# 05-Power-V5P0.net
KiCad netlist of a schematic drawn in Altium Designer
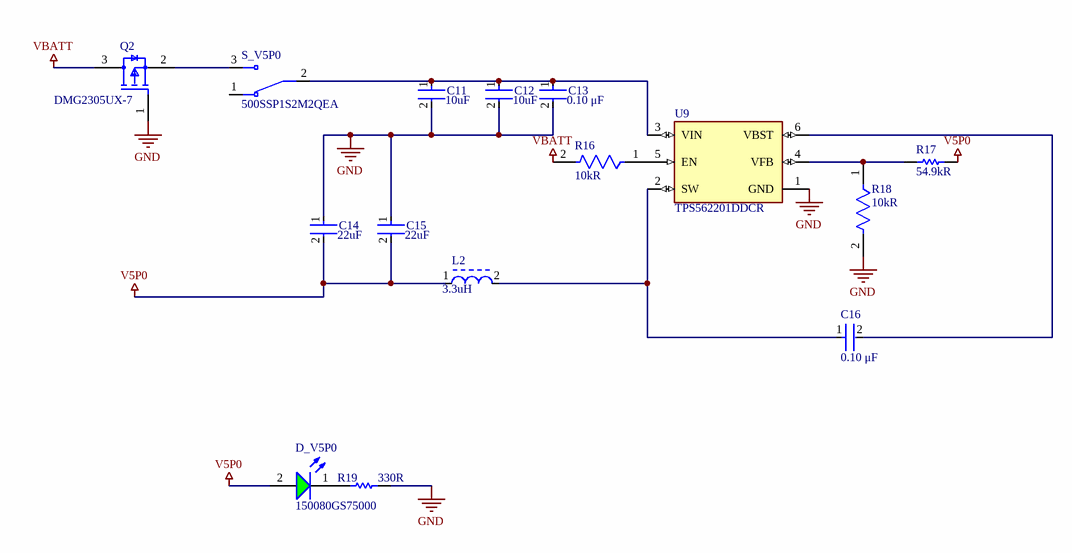
[diagram p0: 05-Power-V5P0.SchDoc]

(export (version "E")
  (design (tool "Eeschema 10.0.6"))
  (components
    (comp (ref "C11")
      (value "GRM21BR61E106KA73L")
      (footprint "FP-GRM21B-0_15-IPC_C")
      (description "Chip Multilayer Ceramic Capacitors for General Purpose, 0805, 10uF, X5R, 15%, 10%, 25V")
      (fields
        (field (name "VOLTAGE") "25V")
        (field (name "CAPACITANCE") "10uF")
        (field (name "TOLERANCE") "10%")
      )
      (libsource (lib "Altium Content Vault") (part "b4654b650e69147ec39a6b967a45e02"))
    )
    (comp (ref "C12")
      (value "GRM21BR61E106KA73L")
      (footprint "FP-GRM21B-0_15-IPC_C")
      (description "Chip Multilayer Ceramic Capacitors for General Purpose, 0805, 10uF, X5R, 15%, 10%, 25V")
      (fields
        (field (name "VOLTAGE") "25V")
        (field (name "CAPACITANCE") "10uF")
        (field (name "TOLERANCE") "10%")
      )
      (libsource (lib "Altium Content Vault") (part "b4654b650e69147ec39a6b967a45e02"))
    )
    (comp (ref "C13")
      (value "0.10 μF")
      (footprint "FP-C0805C-DN-MFG")
      (description "CAP CER 0.1UF 50V X7R 0805")
      (fields
        (field (name "MANUFACTURER PART NUMBER") "C0805C104K5RACTU")
        (field (name "MANUFACTURER") "KEMET")
      )
      (libsource (lib "Altium Content Vault") (part "b4654b650e69147ec39a6b967a45e02"))
    )
    (comp (ref "C14")
      (value "GRM21BR61E226ME44L")
      (footprint "FP-GRM21B-0_2-e0_2_0_7-IPC_B")
      (description "Chip Multilayer Ceramic Capacitors for General Purpose, 0805, 22uF, X5R, 15%, 20%, 25V")
      (fields
        (field (name "TOLERANCE") "20%")
        (field (name "CAPACITANCE") "22uF")
        (field (name "VOLTAGE") "25V")
      )
      (libsource (lib "Altium Content Vault") (part "b4654b650e69147ec39a6b967a45e02"))
    )
    (comp (ref "C15")
      (value "GRM21BR61E226ME44L")
      (footprint "FP-GRM21B-0_2-e0_2_0_7-IPC_B")
      (description "Chip Multilayer Ceramic Capacitors for General Purpose, 0805, 22uF, X5R, 15%, 20%, 25V")
      (fields
        (field (name "TOLERANCE") "20%")
        (field (name "CAPACITANCE") "22uF")
        (field (name "VOLTAGE") "25V")
      )
      (libsource (lib "Altium Content Vault") (part "b4654b650e69147ec39a6b967a45e02"))
    )
    (comp (ref "C16")
      (value "0.10 μF")
      (footprint "FP-C0805C-DN-MFG")
      (description "CAP CER 0.1UF 50V X7R 0805")
      (fields
        (field (name "MANUFACTURER PART NUMBER") "C0805C104K5RACTU")
        (field (name "MANUFACTURER") "KEMET")
      )
      (libsource (lib "Altium Content Vault") (part "b4654b650e69147ec39a6b967a45e02"))
    )
    (comp (ref "D_V5P0")
      (value "150080GS75000")
      (footprint "WL-SMCW_0805_150080xx75000")
      (description "LED GREEN CLEAR 0805 SMD")
      (fields (field (name "MANUFACTURER") "Wurth Electronics"))
      (libsource (lib "Altium Content Vault") (part "LED_Green_2A-1K"))
    )
    (comp (ref "L2")
      (value "SRN6045-3R3Y")
      (footprint "FP-SRN6045-MFG")
      (description "FIXED IND 3.3UH 3.2A 30.2MOHM SM")
      (fields
        (field (name "INDUCTANCE") "3.3uH")
        (field (name "TOLERANCE") "30%")
        (field (name "MANUFACTURER") "Bourns")
      )
      (libsource (lib "Altium Content Vault") (part "e3fba2ffd49a0ea5f20e61e1dfb215d"))
    )
    (comp (ref "Q2")
      (value "DMG2305UX-7")
      (footprint "FP-SOT23-IPC_B")
      (description "MOSFET P-CH 20V 4.2A SOT23")
      (libsource (lib "Altium Content Vault") (part "87831b450059b469d4a68f5364f4496"))
    )
    (comp (ref "R16")
      (value "RMCF0805FT10K0")
      (footprint "FP-RMCF0805-MFG")
      (description "RES 10K OHM 1% 1/8W 0805")
      (fields
        (field (name "TOLERANCE") "1%")
        (field (name "RESISTANCE") "10kR")
        (field (name "MANUFACTURER") "Stackpole Electronics")
      )
      (libsource (lib "Altium Content Vault") (part "1029c3af85768c4190bb7ad29bc67b5"))
    )
    (comp (ref "R17")
      (value "54.9kR")
      (footprint "RESC2013X70X40LL20T20")
      (fields
        (field (name "MANUFACTURER") "Panasonic")
        (field (name "PART NUMBER") "ERJ-6ENF5492V")
        (field (name "TOLERANCE") "1%")
      )
      (libsource (lib "Altium Content Vault") (part "RES"))
    )
    (comp (ref "R18")
      (value "RMCF0805FT10K0")
      (footprint "FP-RMCF0805-MFG")
      (description "RES 10K OHM 1% 1/8W 0805")
      (fields
        (field (name "TOLERANCE") "1%")
        (field (name "RESISTANCE") "10kR")
        (field (name "MANUFACTURER") "Stackpole Electronics")
      )
      (libsource (lib "Altium Content Vault") (part "1029c3af85768c4190bb7ad29bc67b5"))
    )
    (comp (ref "R19")
      (value "330R")
      (footprint "RESC2013X60X40LL20T25")
      (description "RES SMD 330 OHM 1% 1/8W 0805")
      (fields
        (field (name "MANUFACTURER") "Panasonic")
        (field (name "MANUFACTURER PART NUMBER") "ERJ-6ENF3300V")
      )
      (libsource (lib "Altium Content Vault") (part "RES"))
    )
    (comp (ref "S_V5P0")
      (value "500SSP1S2M2QEA")
      (footprint "mjindal2_pcblib:SW_500SSP1S2M2QEA")
      (description "Slide Switch SPDT Through Hole")
      (libsource (lib "mjindal2_schlib") (part "500SSP1S2M2QEA"))
    )
    (comp (ref "U9")
      (value "TPS562201DDCR")
      (footprint "FP-DDC0006A-IPC_C")
      (description "IC REG BUCK ADJ 2A TSOT23-6")
      (libsource (lib "Altium Content Vault") (part "957e164956730ea4bf6293280af19fc"))
    )
  )
  (nets
    (net (code "1") (name "GND") (class "Default")
      (node (ref "C11") (pin "2") (pinfunction "2_2") (pintype "passive"))
      (node (ref "C12") (pin "2") (pinfunction "2_2") (pintype "passive"))
      (node (ref "C13") (pin "2") (pinfunction "2_2") (pintype "passive"))
      (node (ref "C14") (pin "1") (pinfunction "1_1") (pintype "passive"))
      (node (ref "C15") (pin "1") (pinfunction "1_1") (pintype "passive"))
      (node (ref "Q2") (pin "1") (pinfunction "GATE_1") (pintype "passive"))
      (node (ref "R18") (pin "2") (pinfunction "2_2") (pintype "passive"))
      (node (ref "R19") (pin "1") (pinfunction "1_1") (pintype "passive"))
      (node (ref "U9") (pin "1") (pinfunction "GND_1") (pintype "power_in"))
    )
    (net (code "2") (name "Net-(D_V5P0-K)") (class "Default")
      (node (ref "D_V5P0") (pin "1") (pinfunction "K_1") (pintype "passive"))
      (node (ref "R19") (pin "2") (pinfunction "2_2") (pintype "passive"))
    )
    (net (code "3") (name "Net-(Q2-SOURCE)") (class "Default")
      (node (ref "Q2") (pin "2") (pinfunction "SOURCE_2") (pintype "passive"))
      (node (ref "S_V5P0") (pin "3") (pinfunction "NO_3") (pintype "passive"))
    )
    (net (code "4") (name "Net-(S_V5P0-COM)") (class "Default")
      (node (ref "C11") (pin "1") (pinfunction "1_1") (pintype "passive"))
      (node (ref "C12") (pin "1") (pinfunction "1_1") (pintype "passive"))
      (node (ref "C13") (pin "1") (pinfunction "1_1") (pintype "passive"))
      (node (ref "S_V5P0") (pin "2") (pinfunction "COM_2") (pintype "passive"))
      (node (ref "U9") (pin "3") (pinfunction "VIN_3") (pintype "bidirectional"))
    )
    (net (code "5") (name "Net-(U9-EN)") (class "Default")
      (node (ref "R16") (pin "1") (pinfunction "1_1") (pintype "passive"))
      (node (ref "U9") (pin "5") (pinfunction "EN_5") (pintype "input"))
    )
    (net (code "6") (name "Net-(U9-SW)") (class "Default")
      (node (ref "C16") (pin "1") (pinfunction "1_1") (pintype "passive"))
      (node (ref "L2") (pin "2") (pinfunction "2_2") (pintype "passive"))
      (node (ref "U9") (pin "2") (pinfunction "SW_2") (pintype "bidirectional"))
    )
    (net (code "7") (name "Net-(U9-VBST)") (class "Default")
      (node (ref "C16") (pin "2") (pinfunction "2_2") (pintype "passive"))
      (node (ref "U9") (pin "6") (pinfunction "VBST_6") (pintype "bidirectional"))
    )
    (net (code "8") (name "Net-(U9-VFB)") (class "Default")
      (node (ref "R17") (pin "2") (pinfunction "2_2") (pintype "passive"))
      (node (ref "R18") (pin "1") (pinfunction "1_1") (pintype "passive"))
      (node (ref "U9") (pin "4") (pinfunction "VFB_4") (pintype "bidirectional"))
    )
    (net (code "9") (name "V5P0") (class "Default")
      (node (ref "C14") (pin "2") (pinfunction "2_2") (pintype "passive"))
      (node (ref "C15") (pin "2") (pinfunction "2_2") (pintype "passive"))
      (node (ref "D_V5P0") (pin "2") (pinfunction "A_2") (pintype "passive"))
      (node (ref "L2") (pin "1") (pinfunction "1_1") (pintype "passive"))
      (node (ref "R17") (pin "1") (pinfunction "1_1") (pintype "passive"))
    )
    (net (code "10") (name "VBATT") (class "Default")
      (node (ref "Q2") (pin "3") (pinfunction "DRAIN_3") (pintype "passive"))
      (node (ref "R16") (pin "2") (pinfunction "2_2") (pintype "passive"))
    )
    (net (code "11") (name "unconnected-(S_V5P0-NC-Pad1)") (class "Default")
      (node (ref "S_V5P0") (pin "1") (pinfunction "NC_1") (pintype "passive"))
    )
  )
)
